# accessory_40x40_temp.net
KiCad netlist of a schematic drawn in EAGLE
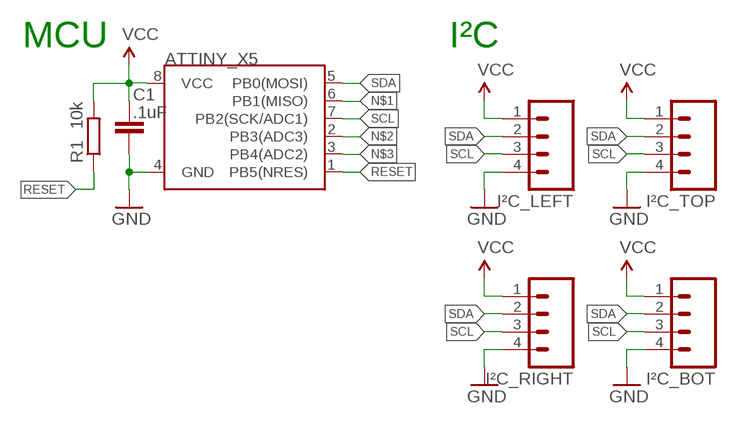
[diagram p0: schematic, sheet 1]

(export (version "E")
  (design (tool "Eeschema 10.0.6"))
  (components
    (comp (ref "ATTINY_X5")
      (value "ATTINY45TINY45-20-SMT")
      (footprint "eagle-import:SO08-EIAJ")
      (libsource (lib "eagle-import") (part "ATTINY45TINY45-20-SMT"))
    )
    (comp (ref "C1")
      (value ".1uF")
      (footprint "eagle-import:C805")
      (libsource (lib "eagle-import") (part "CAPACITOR_NPOL-0805"))
    )
    (comp (ref "I²C_BOT")
      (value "M04PTH")
      (footprint "eagle-import:1X04")
      (libsource (lib "eagle-import") (part "M04PTH"))
    )
    (comp (ref "I²C_LEFT")
      (value "M04PTH")
      (footprint "eagle-import:1X04")
      (libsource (lib "eagle-import") (part "M04PTH"))
    )
    (comp (ref "I²C_RIGHT")
      (value "M04PTH")
      (footprint "eagle-import:1X04")
      (libsource (lib "eagle-import") (part "M04PTH"))
    )
    (comp (ref "I²C_TOP")
      (value "M04PTH")
      (footprint "eagle-import:1X04")
      (libsource (lib "eagle-import") (part "M04PTH"))
    )
    (comp (ref "R1")
      (value "10k")
      (footprint "eagle-import:R805")
      (libsource (lib "eagle-import") (part "RESISTOR-0805R805"))
    )
  )
  (nets
    (net (code "1") (name "GND") (class "Default")
      (node (ref "ATTINY_X5") (pin "4") (pinfunction "GND_4") (pintype "bidirectional"))
      (node (ref "C1") (pin "2") (pinfunction "2_2") (pintype "passive"))
      (node (ref "I²C_BOT") (pin "4") (pinfunction "4_4") (pintype "passive"))
      (node (ref "I²C_LEFT") (pin "4") (pinfunction "4_4") (pintype "passive"))
      (node (ref "I²C_RIGHT") (pin "4") (pinfunction "4_4") (pintype "passive"))
      (node (ref "I²C_TOP") (pin "4") (pinfunction "4_4") (pintype "passive"))
    )
    (net (code "2") (name "N$1") (class "Default")
      (node (ref "ATTINY_X5") (pin "6") (pinfunction "PB1(MISO)_6") (pintype "bidirectional"))
    )
    (net (code "3") (name "N$2") (class "Default")
      (node (ref "ATTINY_X5") (pin "2") (pinfunction "PB3(ADC3)_2") (pintype "bidirectional"))
    )
    (net (code "4") (name "N$3") (class "Default")
      (node (ref "ATTINY_X5") (pin "3") (pinfunction "PB4(ADC2)_3") (pintype "bidirectional"))
    )
    (net (code "5") (name "RESET") (class "Default")
      (node (ref "ATTINY_X5") (pin "1") (pinfunction "PB5(NRES)_1") (pintype "bidirectional"))
      (node (ref "R1") (pin "1") (pinfunction "1_1") (pintype "passive"))
    )
    (net (code "6") (name "SCL") (class "Default")
      (node (ref "ATTINY_X5") (pin "7") (pinfunction "PB2(SCK/ADC1)_7") (pintype "bidirectional"))
      (node (ref "I²C_BOT") (pin "3") (pinfunction "3_3") (pintype "passive"))
      (node (ref "I²C_LEFT") (pin "3") (pinfunction "3_3") (pintype "passive"))
      (node (ref "I²C_RIGHT") (pin "3") (pinfunction "3_3") (pintype "passive"))
      (node (ref "I²C_TOP") (pin "3") (pinfunction "3_3") (pintype "passive"))
    )
    (net (code "7") (name "SDA") (class "Default")
      (node (ref "ATTINY_X5") (pin "5") (pinfunction "PB0(MOSI)_5") (pintype "bidirectional"))
      (node (ref "I²C_BOT") (pin "2") (pinfunction "2_2") (pintype "passive"))
      (node (ref "I²C_LEFT") (pin "2") (pinfunction "2_2") (pintype "passive"))
      (node (ref "I²C_RIGHT") (pin "2") (pinfunction "2_2") (pintype "passive"))
      (node (ref "I²C_TOP") (pin "2") (pinfunction "2_2") (pintype "passive"))
    )
    (net (code "8") (name "VCC") (class "Default")
      (node (ref "ATTINY_X5") (pin "8") (pinfunction "VCC_8") (pintype "bidirectional"))
      (node (ref "C1") (pin "1") (pinfunction "1_1") (pintype "passive"))
      (node (ref "I²C_BOT") (pin "1") (pinfunction "1_1") (pintype "passive"))
      (node (ref "I²C_LEFT") (pin "1") (pinfunction "1_1") (pintype "passive"))
      (node (ref "I²C_RIGHT") (pin "1") (pinfunction "1_1") (pintype "passive"))
      (node (ref "I²C_TOP") (pin "1") (pinfunction "1_1") (pintype "passive"))
      (node (ref "R1") (pin "2") (pinfunction "2_2") (pintype "passive"))
    )
  )
)
